# Apo_Board_2017_PB_MILLABLE.net
KiCad netlist of a schematic drawn in EAGLE
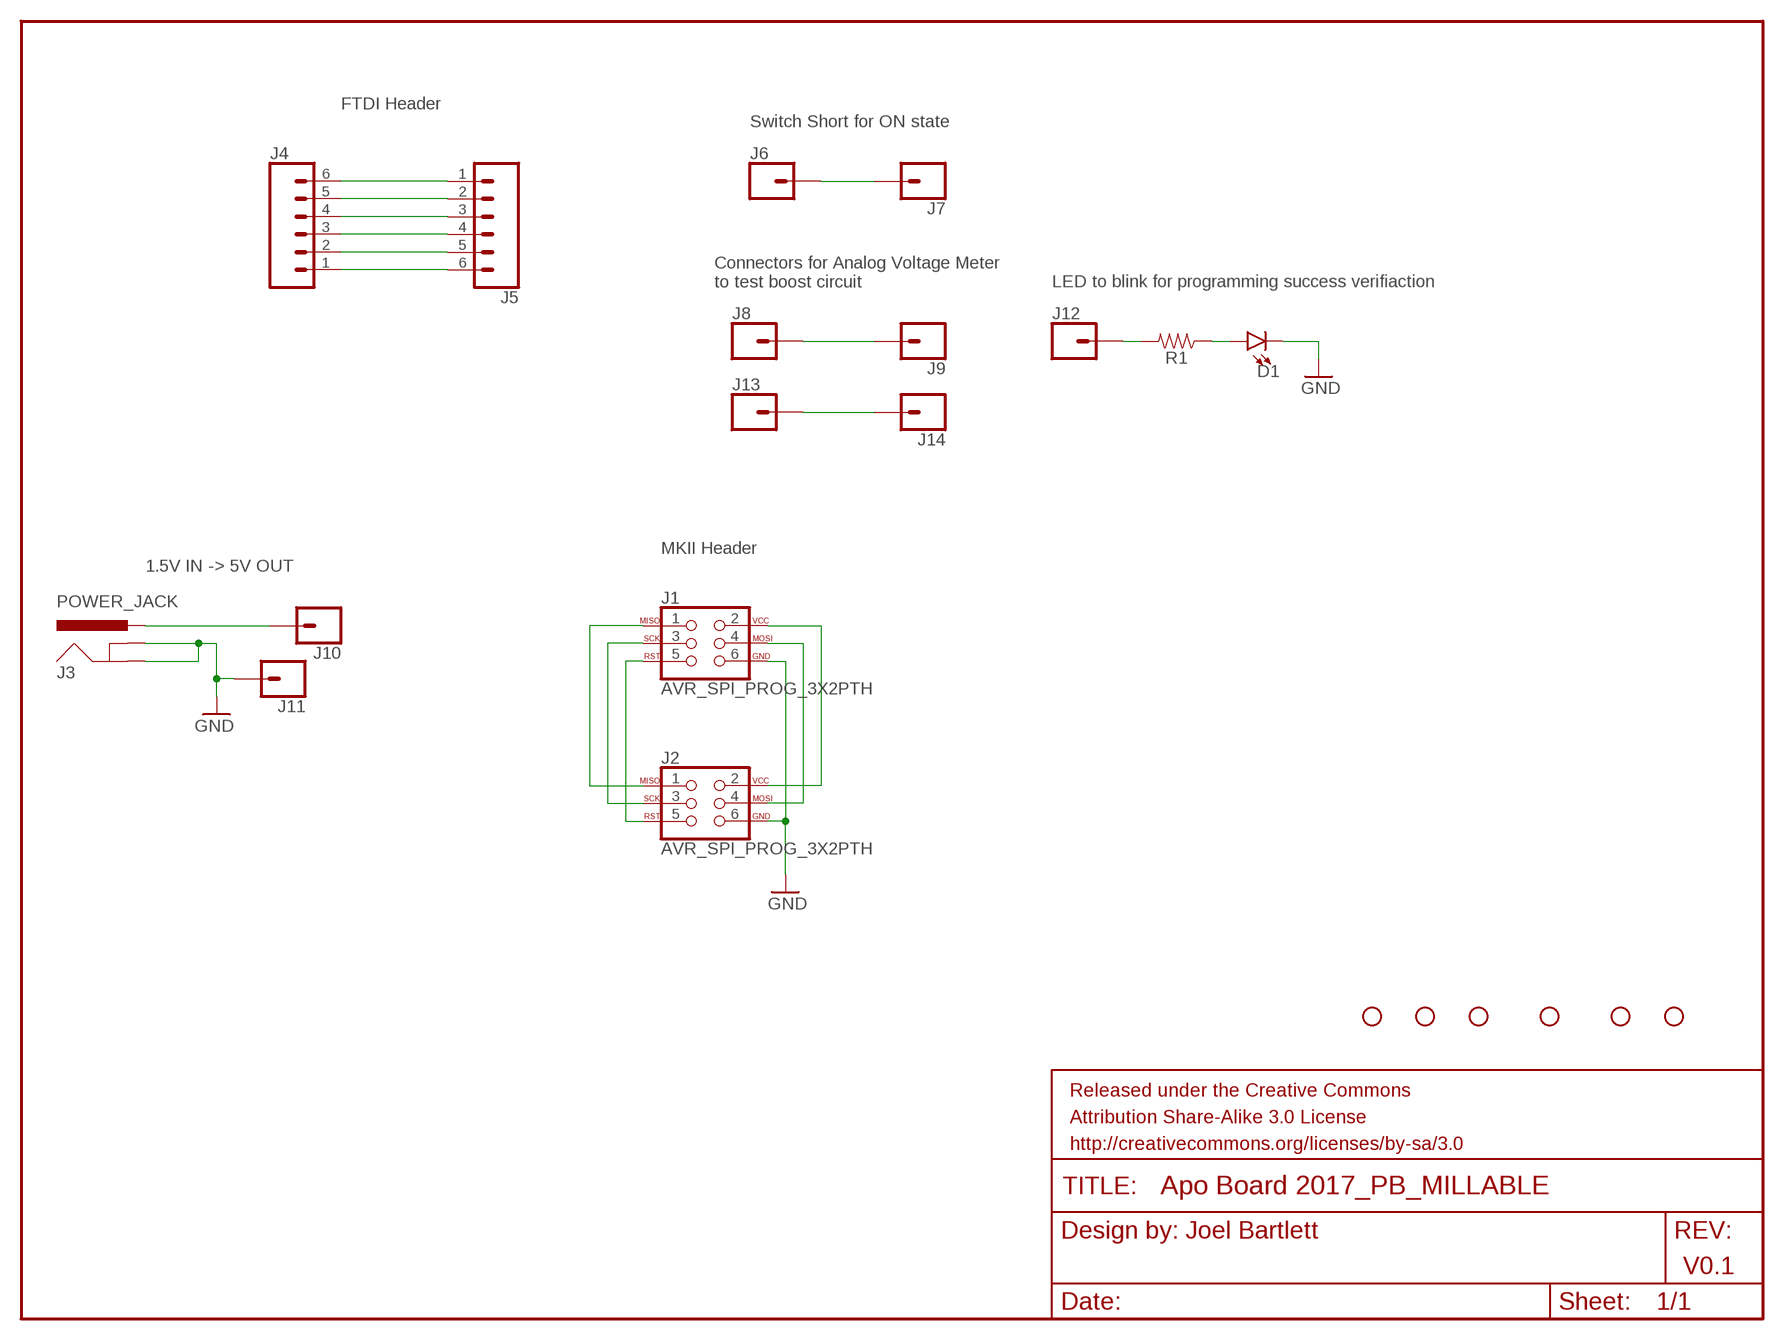
[diagram p0: schematic, sheet 1]

(export (version "E")
  (design (tool "Eeschema 10.0.6"))
  (components
    (comp (ref "D1")
      (value "LED5MM")
      (footprint "eagle-import:LED_5MM")
      (libsource (lib "eagle-import") (part "LED5MM"))
    )
    (comp (ref "FRAME1")
      (value "FRAME-LETTER")
      (footprint "eagle-import:CREATIVE_COMMONS")
      (libsource (lib "eagle-import") (part "FRAME-LETTER"))
    )
    (comp (ref "H1")
      (value "STAND-OFF")
      (footprint "eagle-import:STAND-OFF")
      (libsource (lib "eagle-import") (part "STAND-OFF"))
    )
    (comp (ref "H2")
      (value "STAND-OFF")
      (footprint "eagle-import:STAND-OFF")
      (libsource (lib "eagle-import") (part "STAND-OFF"))
    )
    (comp (ref "H3")
      (value "STAND-OFF")
      (footprint "eagle-import:STAND-OFF")
      (libsource (lib "eagle-import") (part "STAND-OFF"))
    )
    (comp (ref "H4")
      (value "STAND-OFF")
      (footprint "eagle-import:STAND-OFF")
      (libsource (lib "eagle-import") (part "STAND-OFF"))
    )
    (comp (ref "H5")
      (value "STAND-OFF")
      (footprint "eagle-import:STAND-OFF")
      (libsource (lib "eagle-import") (part "STAND-OFF"))
    )
    (comp (ref "H6")
      (value "STAND-OFF")
      (footprint "eagle-import:STAND-OFF")
      (libsource (lib "eagle-import") (part "STAND-OFF"))
    )
    (comp (ref "J1")
      (value "AVR_SPI_PROG_3X2PTH")
      (footprint "eagle-import:2X3")
      (libsource (lib "eagle-import") (part "AVR_SPI_PROG_3X2PTH"))
    )
    (comp (ref "J2")
      (value "AVR_SPI_PROG_3X2PTH")
      (footprint "eagle-import:2X3")
      (libsource (lib "eagle-import") (part "AVR_SPI_PROG_3X2PTH"))
    )
    (comp (ref "J3")
      (value "POWER_JACK")
      (footprint "eagle-import:POWER_JACK_PTH")
      (libsource (lib "eagle-import") (part "POWER_JACK"))
    )
    (comp (ref "J4")
      (value "CONN_06LONGPADS")
      (footprint "eagle-import:1X06_LONGPADS")
      (libsource (lib "eagle-import") (part "CONN_06LONGPADS"))
    )
    (comp (ref "J5")
      (value "CONN_06LONGPADS")
      (footprint "eagle-import:1X06_LONGPADS")
      (libsource (lib "eagle-import") (part "CONN_06LONGPADS"))
    )
    (comp (ref "J6")
      (value "CONN_01PTH_LONGPAD")
      (footprint "eagle-import:1X01_LONGPAD")
      (libsource (lib "eagle-import") (part "CONN_01PTH_LONGPAD"))
    )
    (comp (ref "J7")
      (value "CONN_01PTH_LONGPAD")
      (footprint "eagle-import:1X01_LONGPAD")
      (libsource (lib "eagle-import") (part "CONN_01PTH_LONGPAD"))
    )
    (comp (ref "J8")
      (value "CONN_01PTH_LONGPAD")
      (footprint "eagle-import:1X01_LONGPAD")
      (libsource (lib "eagle-import") (part "CONN_01PTH_LONGPAD"))
    )
    (comp (ref "J9")
      (value "CONN_01PTH_LONGPAD")
      (footprint "eagle-import:1X01_LONGPAD")
      (libsource (lib "eagle-import") (part "CONN_01PTH_LONGPAD"))
    )
    (comp (ref "J10")
      (value "CONN_01PTH_LONGPAD")
      (footprint "eagle-import:1X01_LONGPAD")
      (libsource (lib "eagle-import") (part "CONN_01PTH_LONGPAD"))
    )
    (comp (ref "J11")
      (value "CONN_01PTH_LONGPAD")
      (footprint "eagle-import:1X01_LONGPAD")
      (libsource (lib "eagle-import") (part "CONN_01PTH_LONGPAD"))
    )
    (comp (ref "J12")
      (value "CONN_01PTH_LONGPAD")
      (footprint "eagle-import:1X01_LONGPAD")
      (libsource (lib "eagle-import") (part "CONN_01PTH_LONGPAD"))
    )
    (comp (ref "J13")
      (value "CONN_01PTH_LONGPAD")
      (footprint "eagle-import:1X01_LONGPAD")
      (libsource (lib "eagle-import") (part "CONN_01PTH_LONGPAD"))
    )
    (comp (ref "J14")
      (value "CONN_01PTH_LONGPAD")
      (footprint "eagle-import:1X01_LONGPAD")
      (libsource (lib "eagle-import") (part "CONN_01PTH_LONGPAD"))
    )
    (comp (ref "R1")
      (value "RESISTORAXIAL-0.3-KIT")
      (footprint "eagle-import:AXIAL-0.3-KIT")
      (libsource (lib "eagle-import") (part "RESISTORAXIAL-0.3-KIT"))
    )
  )
  (nets
    (net (code "1") (name "GND") (class "Default")
      (node (ref "D1") (pin "K") (pinfunction "C_K") (pintype "passive"))
      (node (ref "J1") (pin "6") (pinfunction "6_6") (pintype "passive"))
      (node (ref "J11") (pin "1") (pinfunction "1_1") (pintype "passive"))
      (node (ref "J2") (pin "6") (pinfunction "6_6") (pintype "passive"))
      (node (ref "J3") (pin "GND") (pinfunction "GND_GND") (pintype "bidirectional"))
      (node (ref "J3") (pin "GNDBREAK") (pinfunction "GNDBREAK_GNDBREAK") (pintype "bidirectional"))
    )
    (net (code "2") (name "Net-(J1-Pad1)") (class "Default")
      (node (ref "J1") (pin "1") (pinfunction "1_1") (pintype "passive"))
      (node (ref "J2") (pin "1") (pinfunction "1_1") (pintype "passive"))
    )
    (net (code "3") (name "Net-(J1-Pad2)") (class "Default")
      (node (ref "J1") (pin "2") (pinfunction "2_2") (pintype "passive"))
      (node (ref "J2") (pin "2") (pinfunction "2_2") (pintype "passive"))
    )
    (net (code "4") (name "Net-(J1-Pad3)") (class "Default")
      (node (ref "J1") (pin "3") (pinfunction "3_3") (pintype "passive"))
      (node (ref "J2") (pin "3") (pinfunction "3_3") (pintype "passive"))
    )
    (net (code "5") (name "Net-(J1-Pad4)") (class "Default")
      (node (ref "J1") (pin "4") (pinfunction "4_4") (pintype "passive"))
      (node (ref "J2") (pin "4") (pinfunction "4_4") (pintype "passive"))
    )
    (net (code "6") (name "Net-(J1-Pad5)") (class "Default")
      (node (ref "J1") (pin "5") (pinfunction "5_5") (pintype "passive"))
      (node (ref "J2") (pin "5") (pinfunction "5_5") (pintype "passive"))
    )
    (net (code "7") (name "Net-(J4-Pad1)") (class "Default")
      (node (ref "J4") (pin "1") (pinfunction "1_1") (pintype "passive"))
      (node (ref "J5") (pin "6") (pinfunction "6_6") (pintype "passive"))
    )
    (net (code "8") (name "Net-(J4-Pad2)") (class "Default")
      (node (ref "J4") (pin "2") (pinfunction "2_2") (pintype "passive"))
      (node (ref "J5") (pin "5") (pinfunction "5_5") (pintype "passive"))
    )
    (net (code "9") (name "Net-(J4-Pad3)") (class "Default")
      (node (ref "J4") (pin "3") (pinfunction "3_3") (pintype "passive"))
      (node (ref "J5") (pin "4") (pinfunction "4_4") (pintype "passive"))
    )
    (net (code "10") (name "Net-(J4-Pad4)") (class "Default")
      (node (ref "J4") (pin "4") (pinfunction "4_4") (pintype "passive"))
      (node (ref "J5") (pin "3") (pinfunction "3_3") (pintype "passive"))
    )
    (net (code "11") (name "Net-(J4-Pad5)") (class "Default")
      (node (ref "J4") (pin "5") (pinfunction "5_5") (pintype "passive"))
      (node (ref "J5") (pin "2") (pinfunction "2_2") (pintype "passive"))
    )
    (net (code "12") (name "Net-(J4-Pad6)") (class "Default")
      (node (ref "J4") (pin "6") (pinfunction "6_6") (pintype "passive"))
      (node (ref "J5") (pin "1") (pinfunction "1_1") (pintype "passive"))
    )
    (net (code "13") (name "Net-(J6-Pad1)") (class "Default")
      (node (ref "J6") (pin "1") (pinfunction "1_1") (pintype "passive"))
      (node (ref "J7") (pin "1") (pinfunction "1_1") (pintype "passive"))
    )
    (net (code "14") (name "Net-(J8-Pad1)") (class "Default")
      (node (ref "J8") (pin "1") (pinfunction "1_1") (pintype "passive"))
      (node (ref "J9") (pin "1") (pinfunction "1_1") (pintype "passive"))
    )
    (net (code "15") (name "Net-(J10-Pad1)") (class "Default")
      (node (ref "J10") (pin "1") (pinfunction "1_1") (pintype "passive"))
      (node (ref "J3") (pin "PWR") (pinfunction "PWR_PWR") (pintype "bidirectional"))
    )
    (net (code "16") (name "Net-(J13-Pad1)") (class "Default")
      (node (ref "J13") (pin "1") (pinfunction "1_1") (pintype "passive"))
      (node (ref "J14") (pin "1") (pinfunction "1_1") (pintype "passive"))
    )
    (net (code "17") (name "Net-(R1-1)") (class "Default")
      (node (ref "D1") (pin "A") (pinfunction "A_A") (pintype "passive"))
      (node (ref "R1") (pin "P$1") (pinfunction "1_P$1") (pintype "passive"))
    )
    (net (code "18") (name "Net-(R1-2)") (class "Default")
      (node (ref "J12") (pin "1") (pinfunction "1_1") (pintype "passive"))
      (node (ref "R1") (pin "P$2") (pinfunction "2_P$2") (pintype "passive"))
    )
  )
)
